# riser-1u-can.net
KiCad netlist of a schematic drawn in EAGLE
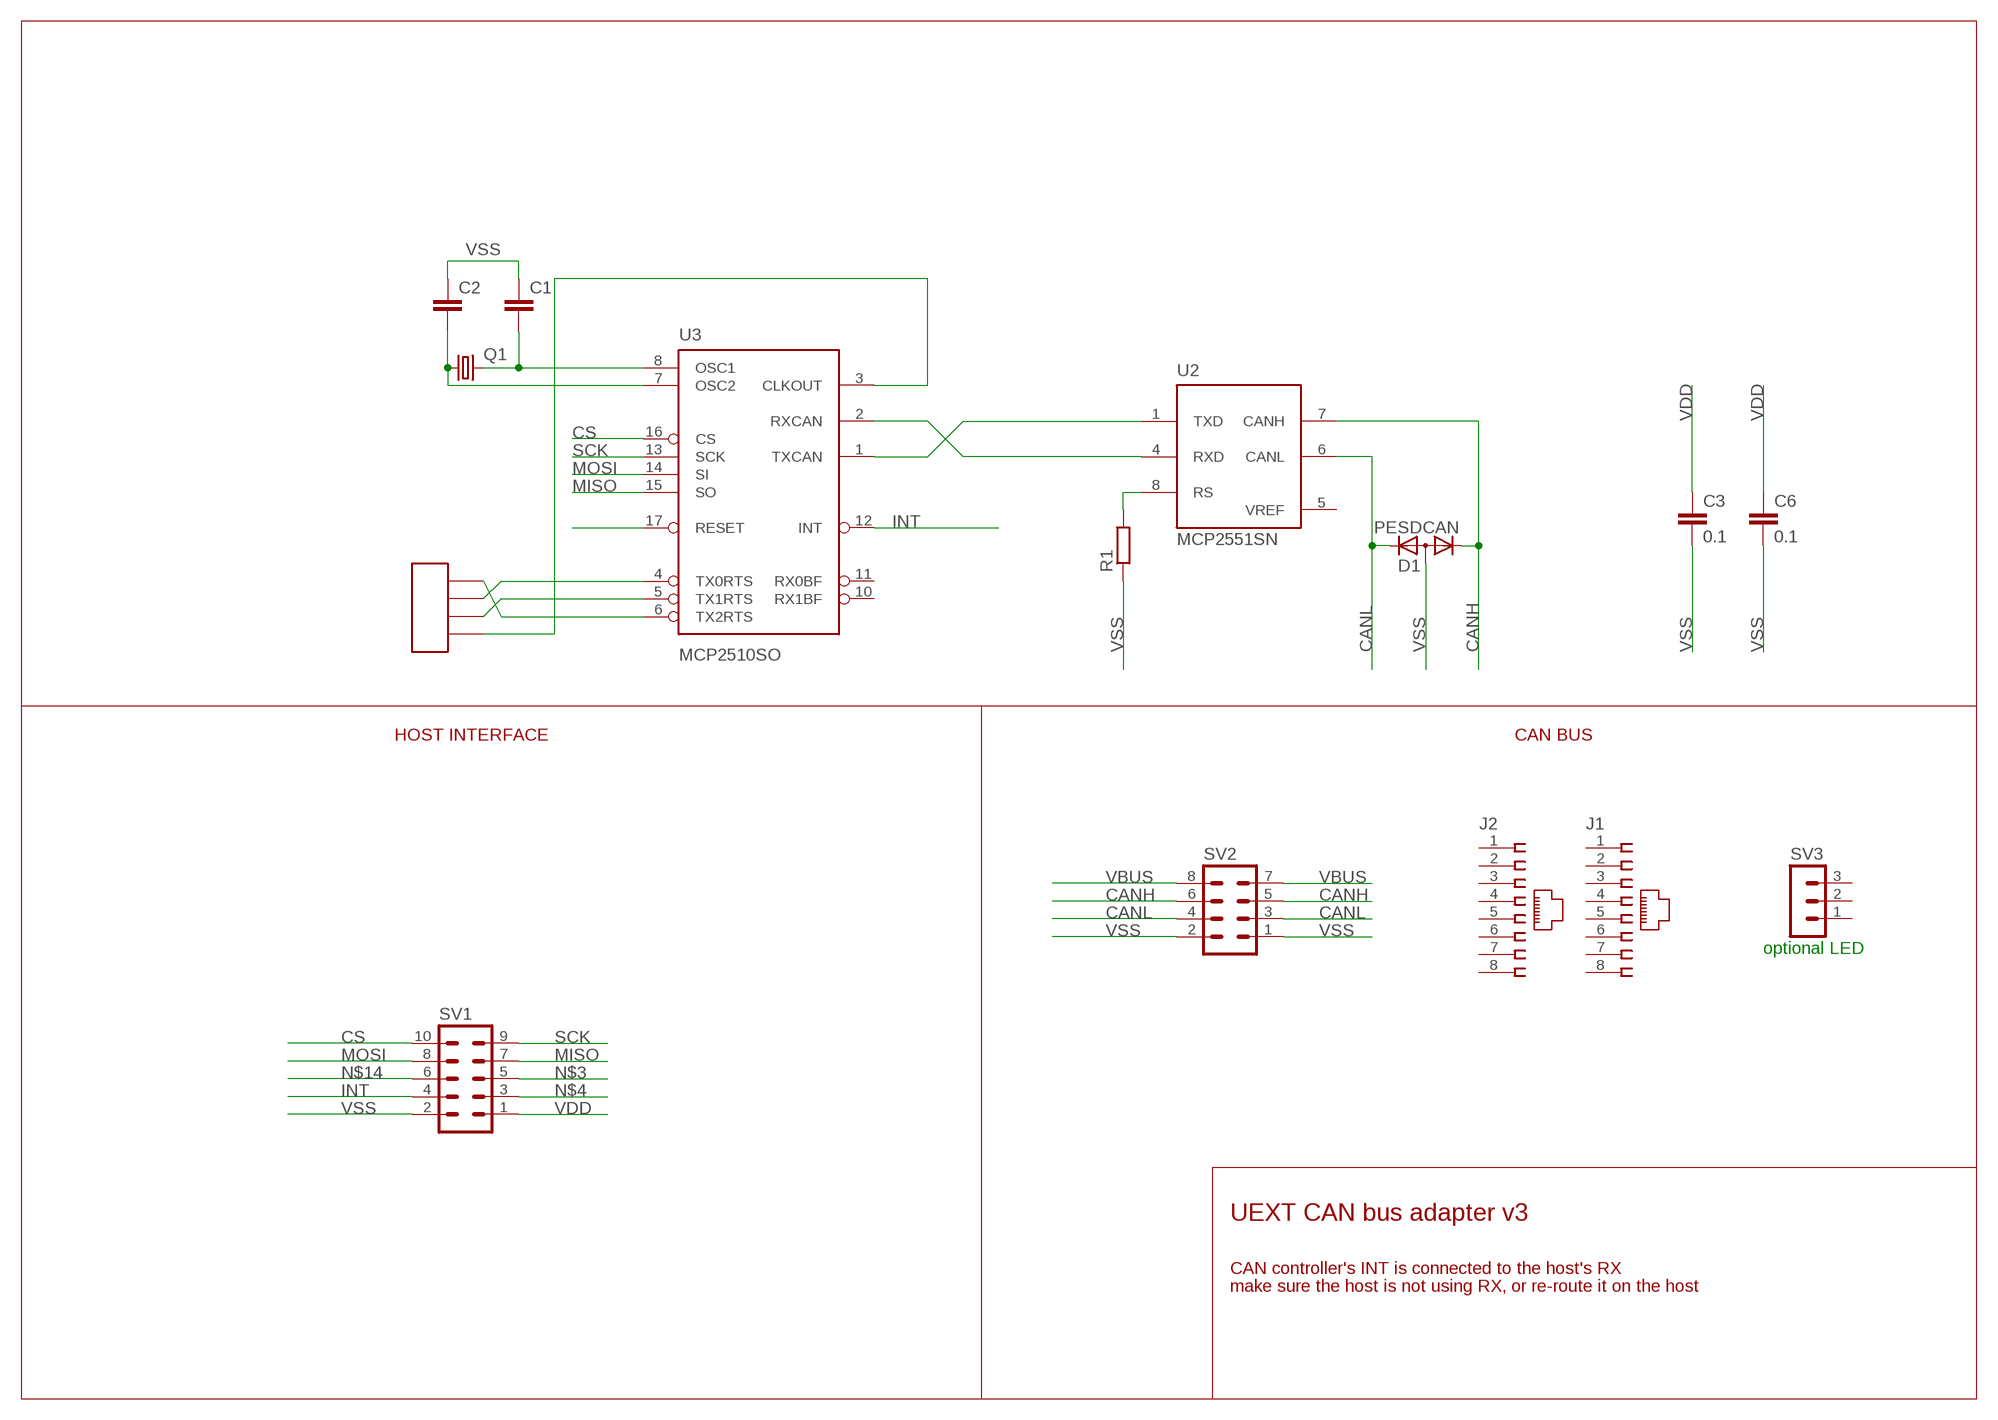
[diagram p0: schematic, sheet 1]

(export (version "E")
  (design (tool "Eeschema 10.0.6"))
  (components
    (comp (ref "C1")
      (value "C-EUC0805")
      (footprint "eagle-import:C0805")
      (libsource (lib "eagle-import") (part "C-EUC0805"))
    )
    (comp (ref "C2")
      (value "C-EUC0805")
      (footprint "eagle-import:C0805")
      (libsource (lib "eagle-import") (part "C-EUC0805"))
    )
    (comp (ref "C3")
      (value "0.1")
      (footprint "eagle-import:C0805")
      (libsource (lib "eagle-import") (part "C-EUC0805"))
    )
    (comp (ref "C6")
      (value "0.1")
      (footprint "eagle-import:C1206")
      (libsource (lib "eagle-import") (part "C-EUC1206"))
    )
    (comp (ref "D1")
      (value "PESDCAN")
      (footprint "eagle-import:SOT23")
      (libsource (lib "eagle-import") (part "DIODE-2CA|ACSOT23"))
    )
    (comp (ref "J1")
      (value "215877-4")
      (footprint "eagle-import:215877-4")
      (libsource (lib "eagle-import") (part "215877-4"))
    )
    (comp (ref "J2")
      (value "215877-4")
      (footprint "eagle-import:215877-4")
      (libsource (lib "eagle-import") (part "215877-4"))
    )
    (comp (ref "Q1")
      (value "CRYSTALHC49S")
      (footprint "eagle-import:HC49_S")
      (libsource (lib "eagle-import") (part "CRYSTALHC49S"))
    )
    (comp (ref "R1")
      (value "R-EU_R0603")
      (footprint "eagle-import:R0603")
      (libsource (lib "eagle-import") (part "R-EU_R0603"))
    )
    (comp (ref "SV1")
      (value "MA05-2")
      (footprint "eagle-import:MA05-2")
      (libsource (lib "eagle-import") (part "MA05-2"))
    )
    (comp (ref "SV2")
      (value "MA04-2")
      (footprint "eagle-import:MA04-2")
      (libsource (lib "eagle-import") (part "MA04-2"))
    )
    (comp (ref "SV3")
      (value "MA03-1")
      (footprint "eagle-import:MA03-1")
      (libsource (lib "eagle-import") (part "MA03-1"))
    )
    (comp (ref "U$2")
      (value "PIN_HEADER_2X2")
      (footprint "eagle-import:PIN_HEADER_2X2")
      (libsource (lib "eagle-import") (part "PIN_HEADER_2X2"))
    )
    (comp (ref "U2")
      (value "MCP2551SN")
      (footprint "eagle-import:SO-08")
      (libsource (lib "eagle-import") (part "MCP2551SN"))
    )
    (comp (ref "U3")
      (value "MCP2510SO")
      (footprint "eagle-import:SO-18W")
      (libsource (lib "eagle-import") (part "MCP2510SO"))
    )
  )
  (nets
    (net (code "1") (name "/CANH") (class "Default")
      (node (ref "D1") (pin "1") (pinfunction "K1_1") (pintype "passive"))
      (node (ref "SV2") (pin "5") (pinfunction "5_5") (pintype "passive"))
      (node (ref "SV2") (pin "6") (pinfunction "6_6") (pintype "passive"))
      (node (ref "U2") (pin "7") (pinfunction "CANH_7") (pintype "bidirectional"))
    )
    (net (code "2") (name "/CANL") (class "Default")
      (node (ref "D1") (pin "2") (pinfunction "K2_2") (pintype "passive"))
      (node (ref "SV2") (pin "3") (pinfunction "3_3") (pintype "passive"))
      (node (ref "SV2") (pin "4") (pinfunction "4_4") (pintype "passive"))
      (node (ref "U2") (pin "6") (pinfunction "CANL_6") (pintype "bidirectional"))
    )
    (net (code "3") (name "/CS") (class "Default")
      (node (ref "SV1") (pin "10") (pinfunction "10_10") (pintype "passive"))
      (node (ref "U3") (pin "16") (pinfunction "CS_16") (pintype "input"))
    )
    (net (code "4") (name "/INT") (class "Default")
      (node (ref "SV1") (pin "4") (pinfunction "4_4") (pintype "passive"))
      (node (ref "U3") (pin "12") (pinfunction "INT_12") (pintype "output"))
    )
    (net (code "5") (name "/MISO") (class "Default")
      (node (ref "SV1") (pin "7") (pinfunction "7_7") (pintype "passive"))
      (node (ref "U3") (pin "15") (pinfunction "SO_15") (pintype "output"))
    )
    (net (code "6") (name "/MOSI") (class "Default")
      (node (ref "SV1") (pin "8") (pinfunction "8_8") (pintype "passive"))
      (node (ref "U3") (pin "14") (pinfunction "SI_14") (pintype "input"))
    )
    (net (code "7") (name "/N$3") (class "Default")
      (node (ref "SV1") (pin "5") (pinfunction "5_5") (pintype "passive"))
    )
    (net (code "8") (name "/N$4") (class "Default")
      (node (ref "SV1") (pin "3") (pinfunction "3_3") (pintype "passive"))
    )
    (net (code "9") (name "/N$14") (class "Default")
      (node (ref "SV1") (pin "6") (pinfunction "6_6") (pintype "passive"))
    )
    (net (code "10") (name "/SCK") (class "Default")
      (node (ref "SV1") (pin "9") (pinfunction "9_9") (pintype "passive"))
      (node (ref "U3") (pin "13") (pinfunction "SCK_13") (pintype "input"))
    )
    (net (code "11") (name "/VBUS") (class "Default")
      (node (ref "SV2") (pin "7") (pinfunction "7_7") (pintype "passive"))
      (node (ref "SV2") (pin "8") (pinfunction "8_8") (pintype "passive"))
    )
    (net (code "12") (name "/VDD") (class "Default")
      (node (ref "C3") (pin "1") (pinfunction "1_1") (pintype "passive"))
      (node (ref "C6") (pin "1") (pinfunction "1_1") (pintype "passive"))
      (node (ref "SV1") (pin "1") (pinfunction "1_1") (pintype "passive"))
    )
    (net (code "13") (name "/VREF") (class "Default")
      (node (ref "U2") (pin "5") (pinfunction "VREF_5") (pintype "power_in"))
    )
    (net (code "14") (name "/VSS") (class "Default")
      (node (ref "C1") (pin "1") (pinfunction "1_1") (pintype "passive"))
      (node (ref "C2") (pin "1") (pinfunction "1_1") (pintype "passive"))
      (node (ref "C3") (pin "2") (pinfunction "2_2") (pintype "passive"))
      (node (ref "C6") (pin "2") (pinfunction "2_2") (pintype "passive"))
      (node (ref "D1") (pin "3") (pinfunction "A_3") (pintype "passive"))
      (node (ref "R1") (pin "1") (pinfunction "1_1") (pintype "passive"))
      (node (ref "SV1") (pin "2") (pinfunction "2_2") (pintype "passive"))
      (node (ref "SV2") (pin "1") (pinfunction "1_1") (pintype "passive"))
      (node (ref "SV2") (pin "2") (pinfunction "2_2") (pintype "passive"))
    )
    (net (code "15") (name "Net-(U2A-RS)") (class "Default")
      (node (ref "R1") (pin "2") (pinfunction "2_2") (pintype "passive"))
      (node (ref "U2") (pin "8") (pinfunction "RS_8") (pintype "input"))
    )
    (net (code "16") (name "Net-(U2A-RXD)") (class "Default")
      (node (ref "U2") (pin "4") (pinfunction "RXD_4") (pintype "output"))
      (node (ref "U3") (pin "2") (pinfunction "RXCAN_2") (pintype "input"))
    )
    (net (code "17") (name "Net-(U2A-TXD)") (class "Default")
      (node (ref "U2") (pin "1") (pinfunction "TXD_1") (pintype "input"))
      (node (ref "U3") (pin "1") (pinfunction "TXCAN_1") (pintype "output"))
    )
    (net (code "18") (name "Net-(U3A-CLKOUT)") (class "Default")
      (node (ref "U$2") (pin "P$4") (pinfunction "P$4_P$4") (pintype "bidirectional"))
      (node (ref "U3") (pin "3") (pinfunction "CLKOUT_3") (pintype "output"))
    )
    (net (code "19") (name "Net-(U3A-OSC1)") (class "Default")
      (node (ref "C1") (pin "2") (pinfunction "2_2") (pintype "passive"))
      (node (ref "Q1") (pin "2") (pinfunction "2_2") (pintype "passive"))
      (node (ref "U3") (pin "8") (pinfunction "OSC1_8") (pintype "input"))
    )
    (net (code "20") (name "Net-(U3A-OSC2)") (class "Default")
      (node (ref "C2") (pin "2") (pinfunction "2_2") (pintype "passive"))
      (node (ref "Q1") (pin "1") (pinfunction "1_1") (pintype "passive"))
      (node (ref "U3") (pin "7") (pinfunction "OSC2_7") (pintype "output"))
    )
    (net (code "21") (name "Net-(U3A-TX0RTS)") (class "Default")
      (node (ref "U$2") (pin "P$2") (pinfunction "P$2_P$2") (pintype "bidirectional"))
      (node (ref "U3") (pin "4") (pinfunction "TX0RTS_4") (pintype "input"))
    )
    (net (code "22") (name "Net-(U3A-TX1RTS)") (class "Default")
      (node (ref "U$2") (pin "P$3") (pinfunction "P$3_P$3") (pintype "bidirectional"))
      (node (ref "U3") (pin "5") (pinfunction "TX1RTS_5") (pintype "input"))
    )
    (net (code "23") (name "Net-(U3A-TX2RTS)") (class "Default")
      (node (ref "U$2") (pin "P$1") (pinfunction "P$1_P$1") (pintype "bidirectional"))
      (node (ref "U3") (pin "6") (pinfunction "TX2RTS_6") (pintype "input"))
    )
    (net (code "24") (name "unconnected-(J1-Pad1)") (class "Default")
      (node (ref "J1") (pin "1") (pinfunction "1_1") (pintype "passive"))
    )
    (net (code "25") (name "unconnected-(J1-Pad2)") (class "Default")
      (node (ref "J1") (pin "2") (pinfunction "2_2") (pintype "passive"))
    )
    (net (code "26") (name "unconnected-(J1-Pad3)") (class "Default")
      (node (ref "J1") (pin "3") (pinfunction "3_3") (pintype "passive"))
    )
    (net (code "27") (name "unconnected-(J1-Pad4)") (class "Default")
      (node (ref "J1") (pin "4") (pinfunction "4_4") (pintype "passive"))
    )
    (net (code "28") (name "unconnected-(J1-Pad5)") (class "Default")
      (node (ref "J1") (pin "5") (pinfunction "5_5") (pintype "passive"))
    )
    (net (code "29") (name "unconnected-(J1-Pad6)") (class "Default")
      (node (ref "J1") (pin "6") (pinfunction "6_6") (pintype "passive"))
    )
    (net (code "30") (name "unconnected-(J1-Pad7)") (class "Default")
      (node (ref "J1") (pin "7") (pinfunction "7_7") (pintype "passive"))
    )
    (net (code "31") (name "unconnected-(J1-Pad8)") (class "Default")
      (node (ref "J1") (pin "8") (pinfunction "8_8") (pintype "passive"))
    )
    (net (code "32") (name "unconnected-(J2-Pad1)") (class "Default")
      (node (ref "J2") (pin "1") (pinfunction "1_1") (pintype "passive"))
    )
    (net (code "33") (name "unconnected-(J2-Pad2)") (class "Default")
      (node (ref "J2") (pin "2") (pinfunction "2_2") (pintype "passive"))
    )
    (net (code "34") (name "unconnected-(J2-Pad3)") (class "Default")
      (node (ref "J2") (pin "3") (pinfunction "3_3") (pintype "passive"))
    )
    (net (code "35") (name "unconnected-(J2-Pad4)") (class "Default")
      (node (ref "J2") (pin "4") (pinfunction "4_4") (pintype "passive"))
    )
    (net (code "36") (name "unconnected-(J2-Pad5)") (class "Default")
      (node (ref "J2") (pin "5") (pinfunction "5_5") (pintype "passive"))
    )
    (net (code "37") (name "unconnected-(J2-Pad6)") (class "Default")
      (node (ref "J2") (pin "6") (pinfunction "6_6") (pintype "passive"))
    )
    (net (code "38") (name "unconnected-(J2-Pad7)") (class "Default")
      (node (ref "J2") (pin "7") (pinfunction "7_7") (pintype "passive"))
    )
    (net (code "39") (name "unconnected-(J2-Pad8)") (class "Default")
      (node (ref "J2") (pin "8") (pinfunction "8_8") (pintype "passive"))
    )
    (net (code "40") (name "unconnected-(SV3-Pad1)") (class "Default")
      (node (ref "SV3") (pin "1") (pinfunction "1_1") (pintype "passive"))
    )
    (net (code "41") (name "unconnected-(SV3-Pad2)") (class "Default")
      (node (ref "SV3") (pin "2") (pinfunction "2_2") (pintype "passive"))
    )
    (net (code "42") (name "unconnected-(SV3-Pad3)") (class "Default")
      (node (ref "SV3") (pin "3") (pinfunction "3_3") (pintype "passive"))
    )
    (net (code "43") (name "unconnected-(U3A-RESET-Pad17)") (class "Default")
      (node (ref "U3") (pin "17") (pinfunction "RESET_17") (pintype "input"))
    )
    (net (code "44") (name "unconnected-(U3A-RX0BF-Pad11)") (class "Default")
      (node (ref "U3") (pin "11") (pinfunction "RX0BF_11") (pintype "output"))
    )
    (net (code "45") (name "unconnected-(U3A-RX1BF-Pad10)") (class "Default")
      (node (ref "U3") (pin "10") (pinfunction "RX1BF_10") (pintype "output"))
    )
  )
)
